# 2LCI2C.net
KiCad netlist of a schematic drawn in EAGLE
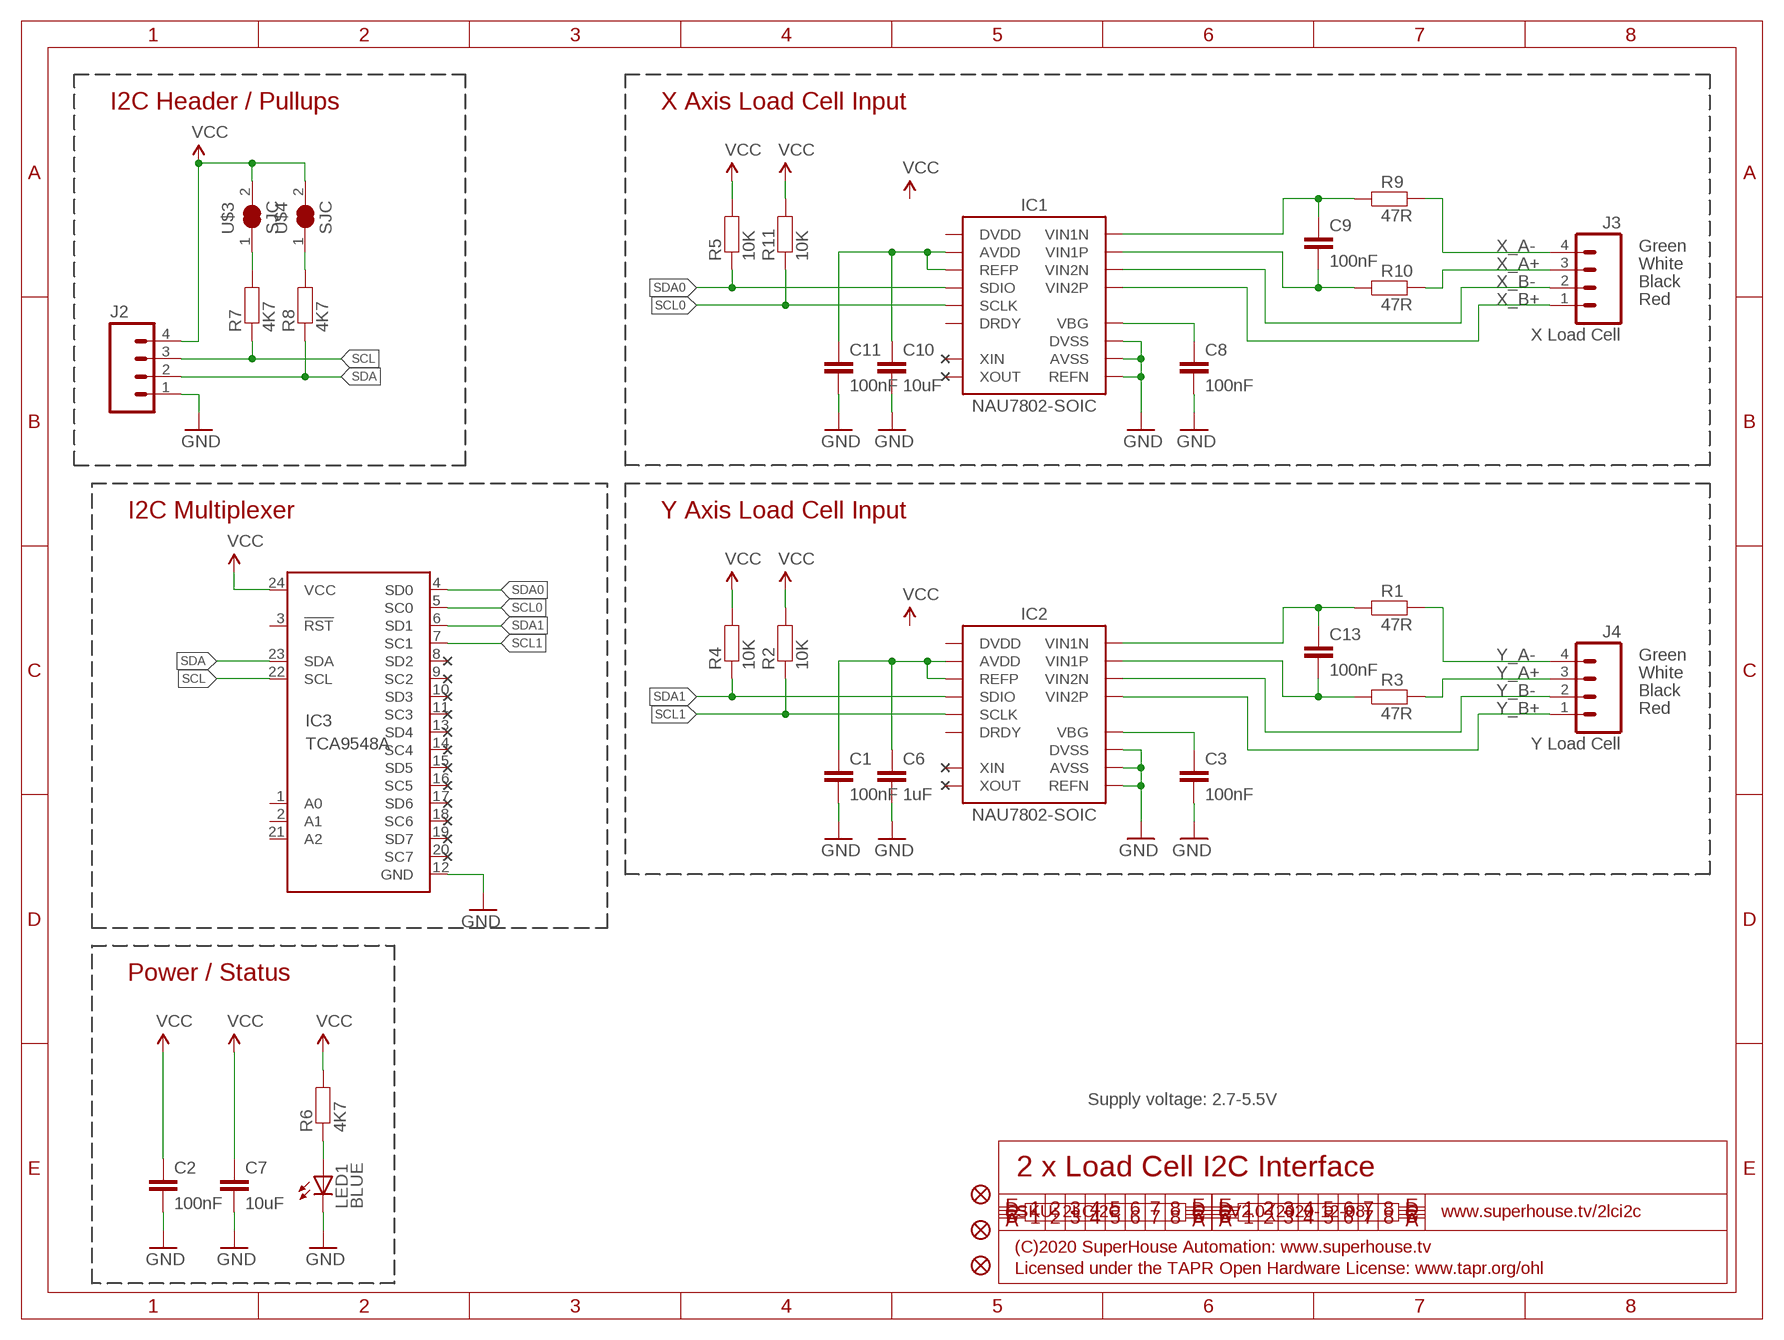
[diagram p0: schematic, sheet 1]

(export (version "E")
  (design (tool "Eeschema 10.0.6"))
  (components
    (comp (ref "C1")
      (value "100nF")
      (footprint "eagle-import:C0603")
      (libsource (lib "eagle-import") (part "CAP0603"))
    )
    (comp (ref "C2")
      (value "100nF")
      (footprint "eagle-import:C0603")
      (libsource (lib "eagle-import") (part "CAP0603"))
    )
    (comp (ref "C3")
      (value "100nF")
      (footprint "eagle-import:C0603")
      (libsource (lib "eagle-import") (part "CAP0603"))
    )
    (comp (ref "C6")
      (value "1uF")
      (footprint "eagle-import:C0805")
      (libsource (lib "eagle-import") (part "CAP0805"))
    )
    (comp (ref "C7")
      (value "10uF")
      (footprint "eagle-import:C0805")
      (libsource (lib "eagle-import") (part "CAP0805"))
    )
    (comp (ref "C8")
      (value "100nF")
      (footprint "eagle-import:C0603")
      (libsource (lib "eagle-import") (part "CAP0603"))
    )
    (comp (ref "C9")
      (value "100nF")
      (footprint "eagle-import:C0603")
      (libsource (lib "eagle-import") (part "CAP0603"))
    )
    (comp (ref "C10")
      (value "10uF")
      (footprint "eagle-import:C0805")
      (libsource (lib "eagle-import") (part "CAP0805"))
    )
    (comp (ref "C11")
      (value "100nF")
      (footprint "eagle-import:C0603")
      (libsource (lib "eagle-import") (part "CAP0603"))
    )
    (comp (ref "C13")
      (value "100nF")
      (footprint "eagle-import:C0603")
      (libsource (lib "eagle-import") (part "CAP0603"))
    )
    (comp (ref "IC1")
      (value "NAU7802-SOIC")
      (footprint "eagle-import:SO16")
      (libsource (lib "eagle-import") (part "NAU7802-SOIC"))
    )
    (comp (ref "IC2")
      (value "NAU7802-SOIC")
      (footprint "eagle-import:SO16")
      (libsource (lib "eagle-import") (part "NAU7802-SOIC"))
    )
    (comp (ref "IC3")
      (value "TCA9548A")
      (footprint "eagle-import:TSSOP24")
      (libsource (lib "eagle-import") (part "TCA9548A"))
    )
    (comp (ref "J2")
      (value "M04-PLAIN")
      (footprint "eagle-import:1X04")
      (libsource (lib "eagle-import") (part "M04-PLAIN"))
    )
    (comp (ref "J3")
      (value "X Load Cell")
      (footprint "eagle-import:1X04-1.27-PLAIN")
      (libsource (lib "eagle-import") (part "M04-1.27-PLAIN"))
    )
    (comp (ref "J4")
      (value "Y Load Cell")
      (footprint "eagle-import:1X04-1.27-PLAIN")
      (libsource (lib "eagle-import") (part "M04-1.27-PLAIN"))
    )
    (comp (ref "LED1")
      (value "BLUE")
      (footprint "eagle-import:LED-0603")
      (libsource (lib "eagle-import") (part "LED0603"))
    )
    (comp (ref "R1")
      (value "47R")
      (footprint "eagle-import:R0603")
      (libsource (lib "eagle-import") (part "RESISTOR0603"))
    )
    (comp (ref "R2")
      (value "10K")
      (footprint "eagle-import:R0603")
      (libsource (lib "eagle-import") (part "RESISTOR0603"))
    )
    (comp (ref "R3")
      (value "47R")
      (footprint "eagle-import:R0603")
      (libsource (lib "eagle-import") (part "RESISTOR0603"))
    )
    (comp (ref "R4")
      (value "10K")
      (footprint "eagle-import:R0603")
      (libsource (lib "eagle-import") (part "RESISTOR0603"))
    )
    (comp (ref "R5")
      (value "10K")
      (footprint "eagle-import:R0603")
      (libsource (lib "eagle-import") (part "RESISTOR0603"))
    )
    (comp (ref "R6")
      (value "4K7")
      (footprint "eagle-import:R0603")
      (libsource (lib "eagle-import") (part "RESISTOR0603"))
    )
    (comp (ref "R7")
      (value "4K7")
      (footprint "eagle-import:R0603")
      (libsource (lib "eagle-import") (part "RESISTOR0603"))
    )
    (comp (ref "R8")
      (value "4K7")
      (footprint "eagle-import:R0603")
      (libsource (lib "eagle-import") (part "RESISTOR0603"))
    )
    (comp (ref "R9")
      (value "47R")
      (footprint "eagle-import:R0603")
      (libsource (lib "eagle-import") (part "RESISTOR0603"))
    )
    (comp (ref "R10")
      (value "47R")
      (footprint "eagle-import:R0603")
      (libsource (lib "eagle-import") (part "RESISTOR0603"))
    )
    (comp (ref "R11")
      (value "10K")
      (footprint "eagle-import:R0603")
      (libsource (lib "eagle-import") (part "RESISTOR0603"))
    )
    (comp (ref "U$3")
      (value "SJC")
      (footprint "eagle-import:SJC")
      (libsource (lib "eagle-import") (part "SJC-NORMAL"))
    )
    (comp (ref "U$4")
      (value "SJC")
      (footprint "eagle-import:SJC")
      (libsource (lib "eagle-import") (part "SJC-NORMAL"))
    )
    (comp (ref "U$5")
      (value "FIDUCIAL1X2.5")
      (footprint "eagle-import:FIDUCIAL-1X2.5")
      (libsource (lib "eagle-import") (part "FIDUCIAL1X2.5"))
    )
    (comp (ref "U$10")
      (value "FIDUCIAL1X2.5")
      (footprint "eagle-import:FIDUCIAL-1X2.5")
      (libsource (lib "eagle-import") (part "FIDUCIAL1X2.5"))
    )
    (comp (ref "U$11")
      (value "FIDUCIAL1X2.5")
      (footprint "eagle-import:FIDUCIAL-1X2.5")
      (libsource (lib "eagle-import") (part "FIDUCIAL1X2.5"))
    )
  )
  (nets
    (net (code "1") (name "/X_A+") (class "Default")
      (node (ref "J3") (pin "3") (pinfunction "3_3") (pintype "passive"))
      (node (ref "R10") (pin "2") (pinfunction "2_2") (pintype "passive"))
    )
    (net (code "2") (name "/X_A-") (class "Default")
      (node (ref "J3") (pin "4") (pinfunction "4_4") (pintype "passive"))
      (node (ref "R9") (pin "2") (pinfunction "2_2") (pintype "passive"))
    )
    (net (code "3") (name "/X_B+") (class "Default")
      (node (ref "IC1") (pin "5") (pinfunction "VIN2P_5") (pintype "bidirectional"))
      (node (ref "J3") (pin "1") (pinfunction "1_1") (pintype "passive"))
    )
    (net (code "4") (name "/X_B-") (class "Default")
      (node (ref "IC1") (pin "4") (pinfunction "VIN2N_4") (pintype "bidirectional"))
      (node (ref "J3") (pin "2") (pinfunction "2_2") (pintype "passive"))
    )
    (net (code "5") (name "/Y_A+") (class "Default")
      (node (ref "J4") (pin "3") (pinfunction "3_3") (pintype "passive"))
      (node (ref "R3") (pin "2") (pinfunction "2_2") (pintype "passive"))
    )
    (net (code "6") (name "/Y_A-") (class "Default")
      (node (ref "J4") (pin "4") (pinfunction "4_4") (pintype "passive"))
      (node (ref "R1") (pin "2") (pinfunction "2_2") (pintype "passive"))
    )
    (net (code "7") (name "/Y_B+") (class "Default")
      (node (ref "IC2") (pin "5") (pinfunction "VIN2P_5") (pintype "bidirectional"))
      (node (ref "J4") (pin "1") (pinfunction "1_1") (pintype "passive"))
    )
    (net (code "8") (name "/Y_B-") (class "Default")
      (node (ref "IC2") (pin "4") (pinfunction "VIN2N_4") (pintype "bidirectional"))
      (node (ref "J4") (pin "2") (pinfunction "2_2") (pintype "passive"))
    )
    (net (code "9") (name "GND") (class "Default")
      (node (ref "C1") (pin "2") (pinfunction "2_2") (pintype "passive"))
      (node (ref "C10") (pin "2") (pinfunction "2_2") (pintype "passive"))
      (node (ref "C11") (pin "2") (pinfunction "2_2") (pintype "passive"))
      (node (ref "C2") (pin "2") (pinfunction "2_2") (pintype "passive"))
      (node (ref "C3") (pin "2") (pinfunction "2_2") (pintype "passive"))
      (node (ref "C6") (pin "2") (pinfunction "2_2") (pintype "passive"))
      (node (ref "C7") (pin "2") (pinfunction "2_2") (pintype "passive"))
      (node (ref "C8") (pin "2") (pinfunction "2_2") (pintype "passive"))
      (node (ref "IC1") (pin "7") (pinfunction "REFN_7") (pintype "bidirectional"))
      (node (ref "IC1") (pin "8") (pinfunction "AVSS_8") (pintype "bidirectional"))
      (node (ref "IC1") (pin "9") (pinfunction "DVSS_9") (pintype "bidirectional"))
      (node (ref "IC2") (pin "7") (pinfunction "REFN_7") (pintype "bidirectional"))
      (node (ref "IC2") (pin "8") (pinfunction "AVSS_8") (pintype "bidirectional"))
      (node (ref "IC2") (pin "9") (pinfunction "DVSS_9") (pintype "bidirectional"))
      (node (ref "IC3") (pin "12") (pinfunction "GND_12") (pintype "bidirectional"))
      (node (ref "J2") (pin "1") (pinfunction "1_1") (pintype "passive"))
      (node (ref "LED1") (pin "C") (pinfunction "C_C") (pintype "passive"))
    )
    (net (code "10") (name "Net-(IC1-AVDD)") (class "Default")
      (node (ref "C10") (pin "1") (pinfunction "1_1") (pintype "passive"))
      (node (ref "C11") (pin "1") (pinfunction "1_1") (pintype "passive"))
      (node (ref "IC1") (pin "1") (pinfunction "REFP_1") (pintype "bidirectional"))
      (node (ref "IC1") (pin "16") (pinfunction "AVDD_16") (pintype "bidirectional"))
    )
    (net (code "11") (name "Net-(IC1-VBG)") (class "Default")
      (node (ref "C8") (pin "1") (pinfunction "1_1") (pintype "passive"))
      (node (ref "IC1") (pin "6") (pinfunction "VBG_6") (pintype "bidirectional"))
    )
    (net (code "12") (name "Net-(IC1-VIN1N)") (class "Default")
      (node (ref "C9") (pin "1") (pinfunction "1_1") (pintype "passive"))
      (node (ref "IC1") (pin "2") (pinfunction "VIN1N_2") (pintype "bidirectional"))
      (node (ref "R9") (pin "1") (pinfunction "1_1") (pintype "passive"))
    )
    (net (code "13") (name "Net-(IC1-VIN1P)") (class "Default")
      (node (ref "C9") (pin "2") (pinfunction "2_2") (pintype "passive"))
      (node (ref "IC1") (pin "3") (pinfunction "VIN1P_3") (pintype "bidirectional"))
      (node (ref "R10") (pin "1") (pinfunction "1_1") (pintype "passive"))
    )
    (net (code "14") (name "Net-(IC2-AVDD)") (class "Default")
      (node (ref "C1") (pin "1") (pinfunction "1_1") (pintype "passive"))
      (node (ref "C6") (pin "1") (pinfunction "1_1") (pintype "passive"))
      (node (ref "IC2") (pin "1") (pinfunction "REFP_1") (pintype "bidirectional"))
      (node (ref "IC2") (pin "16") (pinfunction "AVDD_16") (pintype "bidirectional"))
    )
    (net (code "15") (name "Net-(IC2-VBG)") (class "Default")
      (node (ref "C3") (pin "1") (pinfunction "1_1") (pintype "passive"))
      (node (ref "IC2") (pin "6") (pinfunction "VBG_6") (pintype "bidirectional"))
    )
    (net (code "16") (name "Net-(IC2-VIN1N)") (class "Default")
      (node (ref "C13") (pin "1") (pinfunction "1_1") (pintype "passive"))
      (node (ref "IC2") (pin "2") (pinfunction "VIN1N_2") (pintype "bidirectional"))
      (node (ref "R1") (pin "1") (pinfunction "1_1") (pintype "passive"))
    )
    (net (code "17") (name "Net-(IC2-VIN1P)") (class "Default")
      (node (ref "C13") (pin "2") (pinfunction "2_2") (pintype "passive"))
      (node (ref "IC2") (pin "3") (pinfunction "VIN1P_3") (pintype "bidirectional"))
      (node (ref "R3") (pin "1") (pinfunction "1_1") (pintype "passive"))
    )
    (net (code "18") (name "Net-(LED1-PadA)") (class "Default")
      (node (ref "LED1") (pin "A") (pinfunction "A_A") (pintype "passive"))
      (node (ref "R6") (pin "1") (pinfunction "1_1") (pintype "passive"))
    )
    (net (code "19") (name "Net-(R7-Pad2)") (class "Default")
      (node (ref "R7") (pin "2") (pinfunction "2_2") (pintype "passive"))
      (node (ref "U$3") (pin "1") (pinfunction "1_1") (pintype "passive"))
    )
    (net (code "20") (name "Net-(R8-Pad2)") (class "Default")
      (node (ref "R8") (pin "2") (pinfunction "2_2") (pintype "passive"))
      (node (ref "U$4") (pin "1") (pinfunction "1_1") (pintype "passive"))
    )
    (net (code "21") (name "SCL") (class "Default")
      (node (ref "IC3") (pin "22") (pinfunction "SCL_22") (pintype "bidirectional"))
      (node (ref "J2") (pin "3") (pinfunction "3_3") (pintype "passive"))
      (node (ref "R7") (pin "1") (pinfunction "1_1") (pintype "passive"))
    )
    (net (code "22") (name "SCL0") (class "Default")
      (node (ref "IC1") (pin "13") (pinfunction "SCLK_13") (pintype "bidirectional"))
      (node (ref "IC3") (pin "5") (pinfunction "SC0_5") (pintype "bidirectional"))
      (node (ref "R11") (pin "1") (pinfunction "1_1") (pintype "passive"))
    )
    (net (code "23") (name "SCL1") (class "Default")
      (node (ref "IC2") (pin "13") (pinfunction "SCLK_13") (pintype "bidirectional"))
      (node (ref "IC3") (pin "7") (pinfunction "SC1_7") (pintype "bidirectional"))
      (node (ref "R2") (pin "1") (pinfunction "1_1") (pintype "passive"))
    )
    (net (code "24") (name "SDA") (class "Default")
      (node (ref "IC3") (pin "23") (pinfunction "SDA_23") (pintype "bidirectional"))
      (node (ref "J2") (pin "2") (pinfunction "2_2") (pintype "passive"))
      (node (ref "R8") (pin "1") (pinfunction "1_1") (pintype "passive"))
    )
    (net (code "25") (name "SDA0") (class "Default")
      (node (ref "IC1") (pin "14") (pinfunction "SDIO_14") (pintype "bidirectional"))
      (node (ref "IC3") (pin "4") (pinfunction "SD0_4") (pintype "bidirectional"))
      (node (ref "R5") (pin "1") (pinfunction "1_1") (pintype "passive"))
    )
    (net (code "26") (name "SDA1") (class "Default")
      (node (ref "IC2") (pin "14") (pinfunction "SDIO_14") (pintype "bidirectional"))
      (node (ref "IC3") (pin "6") (pinfunction "SD1_6") (pintype "bidirectional"))
      (node (ref "R4") (pin "1") (pinfunction "1_1") (pintype "passive"))
    )
    (net (code "27") (name "VCC") (class "Default")
      (node (ref "C2") (pin "1") (pinfunction "1_1") (pintype "passive"))
      (node (ref "C7") (pin "1") (pinfunction "1_1") (pintype "passive"))
      (node (ref "IC3") (pin "24") (pinfunction "VCC_24") (pintype "bidirectional"))
      (node (ref "J2") (pin "4") (pinfunction "4_4") (pintype "passive"))
      (node (ref "R11") (pin "2") (pinfunction "2_2") (pintype "passive"))
      (node (ref "R2") (pin "2") (pinfunction "2_2") (pintype "passive"))
      (node (ref "R4") (pin "2") (pinfunction "2_2") (pintype "passive"))
      (node (ref "R5") (pin "2") (pinfunction "2_2") (pintype "passive"))
      (node (ref "R6") (pin "2") (pinfunction "2_2") (pintype "passive"))
      (node (ref "U$3") (pin "2") (pinfunction "2_2") (pintype "passive"))
      (node (ref "U$4") (pin "2") (pinfunction "2_2") (pintype "passive"))
    )
    (net (code "28") (name "unconnected-(IC1-DRDY-Pad12)") (class "Default")
      (node (ref "IC1") (pin "12") (pinfunction "DRDY_12") (pintype "bidirectional"))
    )
    (net (code "29") (name "unconnected-(IC1-DVDD-Pad15)") (class "Default")
      (node (ref "IC1") (pin "15") (pinfunction "DVDD_15") (pintype "bidirectional"))
    )
    (net (code "30") (name "unconnected-(IC1-XIN-Pad10)") (class "Default")
      (node (ref "IC1") (pin "10") (pinfunction "XIN_10") (pintype "bidirectional"))
    )
    (net (code "31") (name "unconnected-(IC1-XOUT-Pad11)") (class "Default")
      (node (ref "IC1") (pin "11") (pinfunction "XOUT_11") (pintype "bidirectional"))
    )
    (net (code "32") (name "unconnected-(IC2-DRDY-Pad12)") (class "Default")
      (node (ref "IC2") (pin "12") (pinfunction "DRDY_12") (pintype "bidirectional"))
    )
    (net (code "33") (name "unconnected-(IC2-DVDD-Pad15)") (class "Default")
      (node (ref "IC2") (pin "15") (pinfunction "DVDD_15") (pintype "bidirectional"))
    )
    (net (code "34") (name "unconnected-(IC2-XIN-Pad10)") (class "Default")
      (node (ref "IC2") (pin "10") (pinfunction "XIN_10") (pintype "bidirectional"))
    )
    (net (code "35") (name "unconnected-(IC2-XOUT-Pad11)") (class "Default")
      (node (ref "IC2") (pin "11") (pinfunction "XOUT_11") (pintype "bidirectional"))
    )
    (net (code "36") (name "unconnected-(IC3-A0-Pad1)") (class "Default")
      (node (ref "IC3") (pin "1") (pinfunction "A0_1") (pintype "bidirectional"))
    )
    (net (code "37") (name "unconnected-(IC3-A1-Pad2)") (class "Default")
      (node (ref "IC3") (pin "2") (pinfunction "A1_2") (pintype "bidirectional"))
    )
    (net (code "38") (name "unconnected-(IC3-A2-Pad21)") (class "Default")
      (node (ref "IC3") (pin "21") (pinfunction "A2_21") (pintype "bidirectional"))
    )
    (net (code "39") (name "unconnected-(IC3-SC2-Pad9)") (class "Default")
      (node (ref "IC3") (pin "9") (pinfunction "SC2_9") (pintype "bidirectional"))
    )
    (net (code "40") (name "unconnected-(IC3-SC3-Pad11)") (class "Default")
      (node (ref "IC3") (pin "11") (pinfunction "SC3_11") (pintype "bidirectional"))
    )
    (net (code "41") (name "unconnected-(IC3-SC4-Pad14)") (class "Default")
      (node (ref "IC3") (pin "14") (pinfunction "SC4_14") (pintype "bidirectional"))
    )
    (net (code "42") (name "unconnected-(IC3-SC5-Pad16)") (class "Default")
      (node (ref "IC3") (pin "16") (pinfunction "SC5_16") (pintype "bidirectional"))
    )
    (net (code "43") (name "unconnected-(IC3-SC6-Pad18)") (class "Default")
      (node (ref "IC3") (pin "18") (pinfunction "SC6_18") (pintype "bidirectional"))
    )
    (net (code "44") (name "unconnected-(IC3-SC7-Pad20)") (class "Default")
      (node (ref "IC3") (pin "20") (pinfunction "SC7_20") (pintype "bidirectional"))
    )
    (net (code "45") (name "unconnected-(IC3-SD2-Pad8)") (class "Default")
      (node (ref "IC3") (pin "8") (pinfunction "SD2_8") (pintype "bidirectional"))
    )
    (net (code "46") (name "unconnected-(IC3-SD3-Pad10)") (class "Default")
      (node (ref "IC3") (pin "10") (pinfunction "SD3_10") (pintype "bidirectional"))
    )
    (net (code "47") (name "unconnected-(IC3-SD4-Pad13)") (class "Default")
      (node (ref "IC3") (pin "13") (pinfunction "SD4_13") (pintype "bidirectional"))
    )
    (net (code "48") (name "unconnected-(IC3-SD5-Pad15)") (class "Default")
      (node (ref "IC3") (pin "15") (pinfunction "SD5_15") (pintype "bidirectional"))
    )
    (net (code "49") (name "unconnected-(IC3-SD6-Pad17)") (class "Default")
      (node (ref "IC3") (pin "17") (pinfunction "SD6_17") (pintype "bidirectional"))
    )
    (net (code "50") (name "unconnected-(IC3-SD7-Pad19)") (class "Default")
      (node (ref "IC3") (pin "19") (pinfunction "SD7_19") (pintype "bidirectional"))
    )
    (net (code "51") (name "unconnected-(IC3-~{RST}-Pad3)") (class "Default")
      (node (ref "IC3") (pin "3") (pinfunction "~{RST}_3") (pintype "bidirectional"))
    )
  )
)
